# o_clone_rev_c.net
KiCad netlist of a schematic drawn in EAGLE
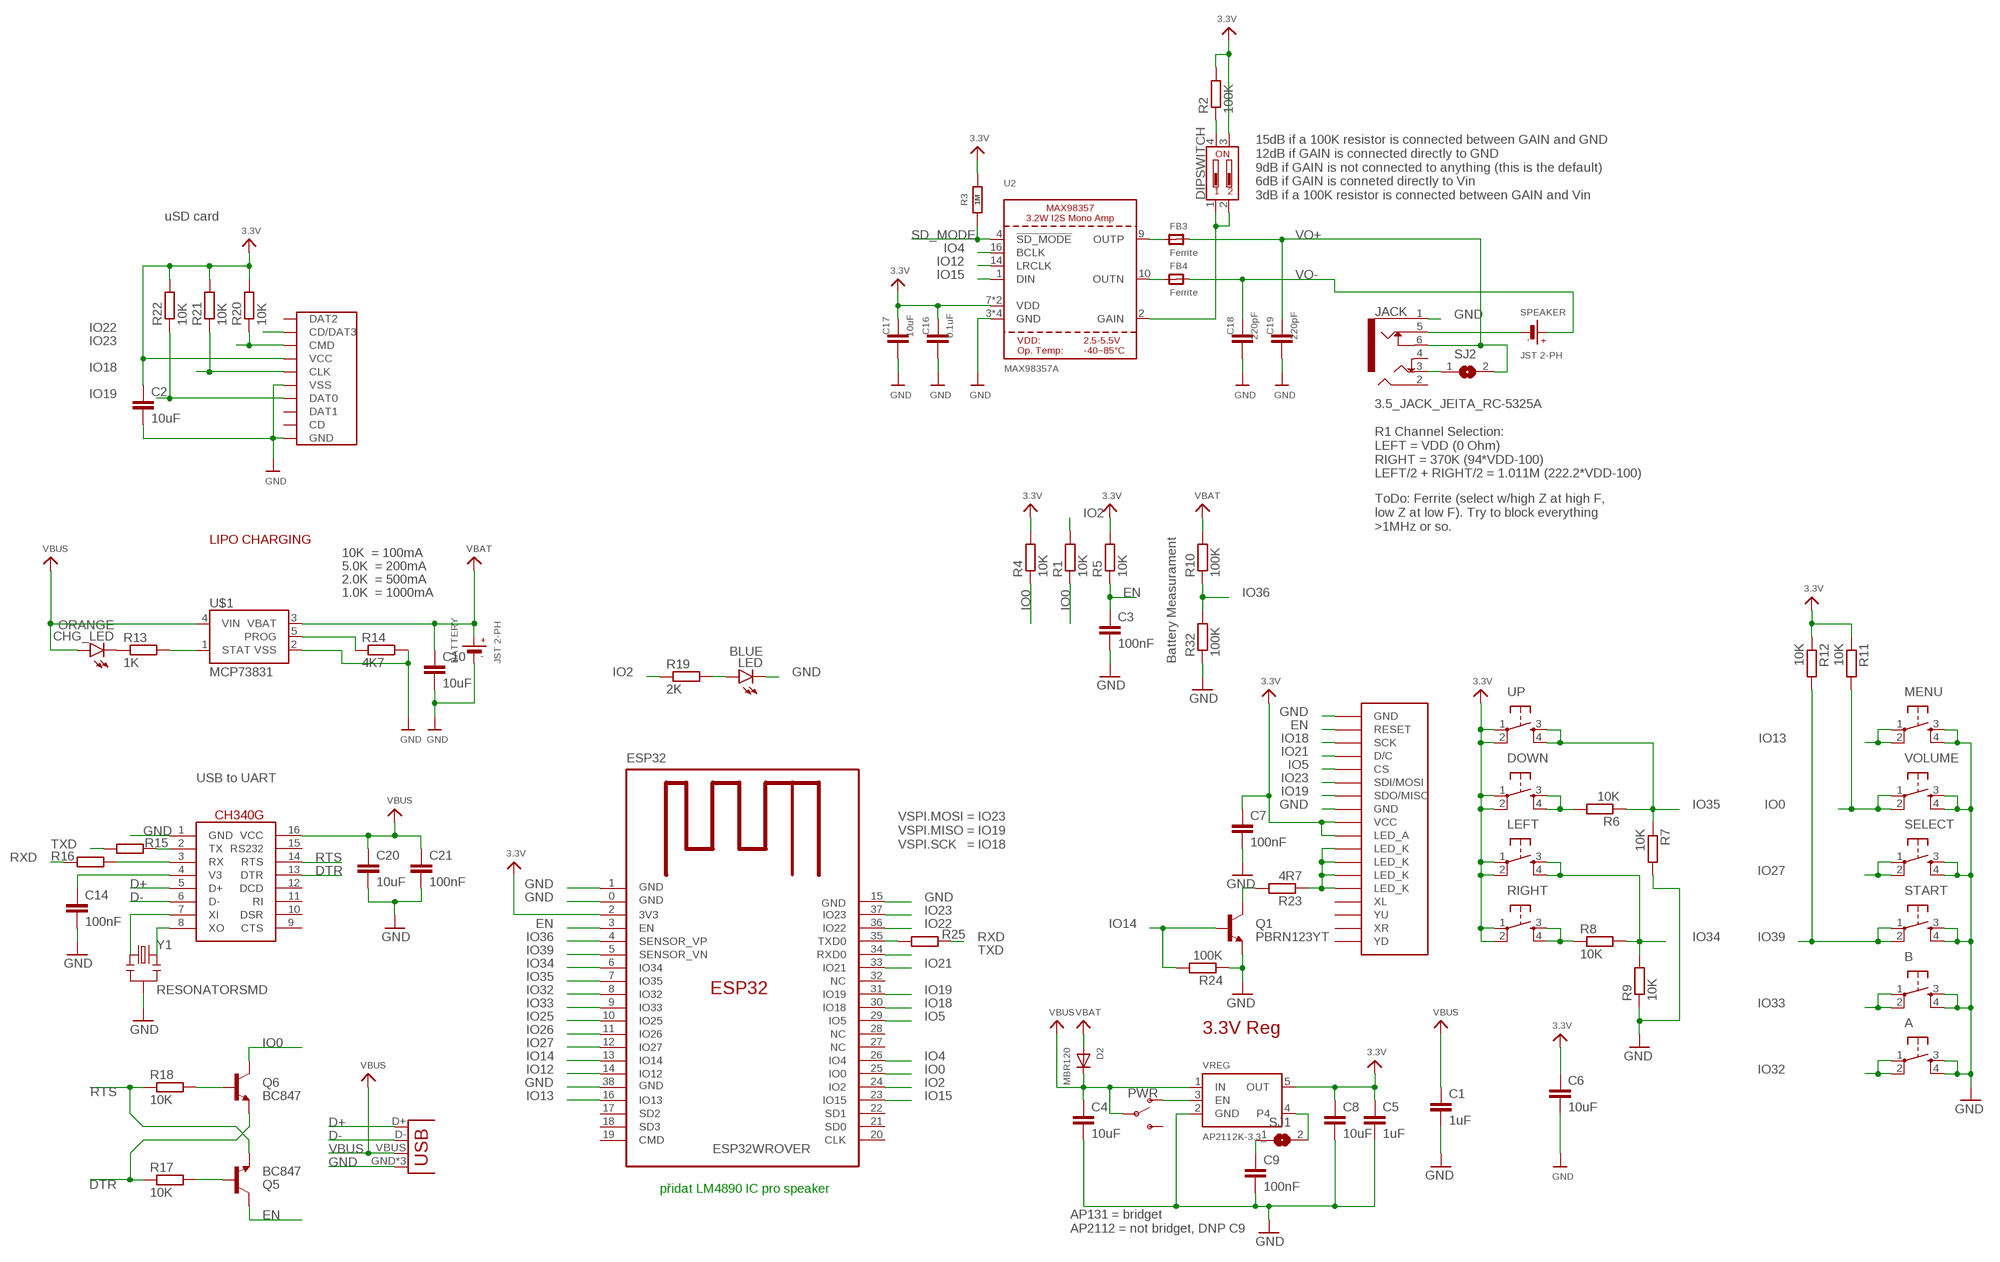
[diagram p0: schematic, sheet 1]

(export (version "E")
  (design (tool "Eeschema 10.0.6"))
  (components
    (comp (ref "A")
      (value "TACTILE_SWITCHE_5X5_MICRO\"")
      (footprint "eagle-import:TACTILE_SWITCH_5X5_MICRO")
      (libsource (lib "eagle-import") (part "TACTILE_SWITCHE_5X5_MICRO{dblquote}"))
    )
    (comp (ref "B")
      (value "TACTILE_SWITCHE_5X5_MICRO\"")
      (footprint "eagle-import:TACTILE_SWITCH_5X5_MICRO")
      (libsource (lib "eagle-import") (part "TACTILE_SWITCHE_5X5_MICRO{dblquote}"))
    )
    (comp (ref "BATTERY")
      (value "JST 2-PH")
      (footprint "eagle-import:JSTPH2")
      (libsource (lib "eagle-import") (part "JST_CONNECTOR"))
    )
    (comp (ref "C1")
      (value "1uF")
      (footprint "eagle-import:C0805")
      (libsource (lib "eagle-import") (part "C-EUC0805"))
    )
    (comp (ref "C2")
      (value "10uF")
      (footprint "eagle-import:C0805")
      (libsource (lib "eagle-import") (part "C-EUC0805"))
    )
    (comp (ref "C3")
      (value "100nF")
      (footprint "eagle-import:C0805")
      (libsource (lib "eagle-import") (part "C-EUC0805"))
    )
    (comp (ref "C4")
      (value "10uF")
      (footprint "eagle-import:C0805")
      (libsource (lib "eagle-import") (part "C-EUC0805"))
    )
    (comp (ref "C5")
      (value "1uF")
      (footprint "eagle-import:C0805")
      (libsource (lib "eagle-import") (part "C-EUC0805"))
    )
    (comp (ref "C6")
      (value "10uF")
      (footprint "eagle-import:C0805")
      (libsource (lib "eagle-import") (part "C-EUC0805"))
    )
    (comp (ref "C7")
      (value "100nF")
      (footprint "eagle-import:C0805")
      (libsource (lib "eagle-import") (part "C-EUC0805"))
    )
    (comp (ref "C8")
      (value "10uF")
      (footprint "eagle-import:C0805")
      (libsource (lib "eagle-import") (part "C-EUC0805"))
    )
    (comp (ref "C9")
      (value "100nF")
      (footprint "eagle-import:C0805")
      (libsource (lib "eagle-import") (part "C-EUC0805"))
    )
    (comp (ref "C10")
      (value "10uF")
      (footprint "eagle-import:C0805")
      (libsource (lib "eagle-import") (part "C-EUC0805"))
    )
    (comp (ref "C14")
      (value "100nF")
      (footprint "eagle-import:C0805")
      (libsource (lib "eagle-import") (part "C-EUC0805"))
    )
    (comp (ref "C16")
      (value "0.1uF")
      (footprint "eagle-import:C0805")
      (libsource (lib "eagle-import") (part "C-EUC0805"))
    )
    (comp (ref "C17")
      (value "10uF")
      (footprint "eagle-import:C0805")
      (libsource (lib "eagle-import") (part "C-EUC0805"))
    )
    (comp (ref "C18")
      (value "220pF")
      (footprint "eagle-import:C0805")
      (libsource (lib "eagle-import") (part "C-EUC0805"))
    )
    (comp (ref "C19")
      (value "220pF")
      (footprint "eagle-import:C0805")
      (libsource (lib "eagle-import") (part "C-EUC0805"))
    )
    (comp (ref "C20")
      (value "10uF")
      (footprint "eagle-import:C0805")
      (libsource (lib "eagle-import") (part "C-EUC0805"))
    )
    (comp (ref "C21")
      (value "100nF")
      (footprint "eagle-import:C0805")
      (libsource (lib "eagle-import") (part "C-EUC0805"))
    )
    (comp (ref "CHG_LED")
      (value "ORANGE")
      (footprint "eagle-import:CHIPLED_0805")
      (libsource (lib "eagle-import") (part "LEDCHIPLED_0805"))
    )
    (comp (ref "D2")
      (value "MBR120")
      (footprint "eagle-import:SOD-123")
      (libsource (lib "eagle-import") (part "DIODESOD-123"))
    )
    (comp (ref "DIPSWITCH")
      (value "DIP-02-SMD-50MIL")
      (footprint "eagle-import:DIPSWITCH-02-50MIL")
      (libsource (lib "eagle-import") (part "DIP-02-SMD-50MIL"))
    )
    (comp (ref "DOWN")
      (value "TACTILE_SWITCHE_5X5_MICRO\"")
      (footprint "eagle-import:TACTILE_SWITCH_5X5_MICRO")
      (libsource (lib "eagle-import") (part "TACTILE_SWITCHE_5X5_MICRO{dblquote}"))
    )
    (comp (ref "ESP32")
      (value "ESP32WROVER")
      (footprint "eagle-import:ESP32WROVER")
      (libsource (lib "eagle-import") (part "ESP32WROVER"))
    )
    (comp (ref "FB3")
      (value "Ferrite")
      (footprint "eagle-import:0805")
      (libsource (lib "eagle-import") (part "FERRITE0805"))
    )
    (comp (ref "FB4")
      (value "Ferrite")
      (footprint "eagle-import:0805")
      (libsource (lib "eagle-import") (part "FERRITE0805"))
    )
    (comp (ref "JACK")
      (value "3.5_JACK_JEITA_RC-5325A")
      (footprint "eagle-import:3.5_JACK_JEITA_RC-5325A")
      (libsource (lib "eagle-import") (part "3.5_JACK_JEITA_RC-5325A"))
    )
    (comp (ref "LCD")
      (value "ILI9341_3.2LCD_")
      (footprint "eagle-import:LI9341_3.2LCD")
      (libsource (lib "eagle-import") (part "ILI9341_3.2LCD_"))
    )
    (comp (ref "LED")
      (value "BLUE")
      (footprint "eagle-import:CHIPLED_0805")
      (libsource (lib "eagle-import") (part "LEDCHIPLED_0805"))
    )
    (comp (ref "LEFT")
      (value "TACTILE_SWITCHE_5X5_MICRO\"")
      (footprint "eagle-import:TACTILE_SWITCH_5X5_MICRO")
      (libsource (lib "eagle-import") (part "TACTILE_SWITCHE_5X5_MICRO{dblquote}"))
    )
    (comp (ref "MENU")
      (value "TACTILE_SWITCHE_5X5_MICRO\"")
      (footprint "eagle-import:TACTILE_SWITCH_5X5_MICRO")
      (libsource (lib "eagle-import") (part "TACTILE_SWITCHE_5X5_MICRO{dblquote}"))
    )
    (comp (ref "PWR")
      (value "SWITCH-SPDT-SMD-RIGHT-ANGLE")
      (footprint "eagle-import:SWITCH_SPST_SMD_A")
      (libsource (lib "eagle-import") (part "SWITCH-SPDT-SMD-RIGHT-ANGLE"))
    )
    (comp (ref "Q1")
      (value "PBRN123YT")
      (footprint "eagle-import:SOT23-3")
      (libsource (lib "eagle-import") (part "TRANSISTOR_NPNSOT23-3"))
    )
    (comp (ref "Q5")
      (value "BC847")
      (footprint "eagle-import:SOT23-3")
      (libsource (lib "eagle-import") (part "TRANSISTOR_NPNSOT23-3"))
    )
    (comp (ref "Q6")
      (value "BC847")
      (footprint "eagle-import:SOT23-3")
      (libsource (lib "eagle-import") (part "TRANSISTOR_NPNSOT23-3"))
    )
    (comp (ref "R1")
      (value "10K")
      (footprint "eagle-import:R0805")
      (libsource (lib "eagle-import") (part "R-EU_R0805"))
    )
    (comp (ref "R2")
      (value "100K")
      (footprint "eagle-import:R0805")
      (libsource (lib "eagle-import") (part "R-EU_R0805"))
    )
    (comp (ref "R3")
      (value "1M")
      (footprint "eagle-import:R0805")
      (libsource (lib "eagle-import") (part "R-EU_R0805"))
    )
    (comp (ref "R4")
      (value "10K")
      (footprint "eagle-import:R0805")
      (libsource (lib "eagle-import") (part "R-EU_R0805"))
    )
    (comp (ref "R5")
      (value "10K")
      (footprint "eagle-import:R0805")
      (libsource (lib "eagle-import") (part "R-EU_R0805"))
    )
    (comp (ref "R6")
      (value "10K")
      (footprint "eagle-import:R0805")
      (libsource (lib "eagle-import") (part "R-EU_R0805"))
    )
    (comp (ref "R7")
      (value "10K")
      (footprint "eagle-import:R0805")
      (libsource (lib "eagle-import") (part "R-EU_R0805"))
    )
    (comp (ref "R8")
      (value "10K")
      (footprint "eagle-import:R0805")
      (libsource (lib "eagle-import") (part "R-EU_R0805"))
    )
    (comp (ref "R9")
      (value "10K")
      (footprint "eagle-import:R0805")
      (libsource (lib "eagle-import") (part "R-EU_R0805"))
    )
    (comp (ref "R10")
      (value "100K")
      (footprint "eagle-import:R0805")
      (libsource (lib "eagle-import") (part "R-EU_R0805"))
    )
    (comp (ref "R11")
      (value "10K")
      (footprint "eagle-import:R0805")
      (libsource (lib "eagle-import") (part "R-EU_R0805"))
    )
    (comp (ref "R12")
      (value "10K")
      (footprint "eagle-import:R0805")
      (libsource (lib "eagle-import") (part "R-EU_R0805"))
    )
    (comp (ref "R13")
      (value "1K")
      (footprint "eagle-import:R0805")
      (libsource (lib "eagle-import") (part "R-EU_R0805"))
    )
    (comp (ref "R14")
      (value "4K7")
      (footprint "eagle-import:R0805")
      (libsource (lib "eagle-import") (part "R-EU_R0805"))
    )
    (comp (ref "R15")
      (value "470R")
      (footprint "eagle-import:R0805")
      (libsource (lib "eagle-import") (part "R-EU_R0805"))
    )
    (comp (ref "R16")
      (value "470R")
      (footprint "eagle-import:R0805")
      (libsource (lib "eagle-import") (part "R-EU_R0805"))
    )
    (comp (ref "R17")
      (value "10K")
      (footprint "eagle-import:R0805")
      (libsource (lib "eagle-import") (part "R-EU_R0805"))
    )
    (comp (ref "R18")
      (value "10K")
      (footprint "eagle-import:R0805")
      (libsource (lib "eagle-import") (part "R-EU_R0805"))
    )
    (comp (ref "R19")
      (value "2K")
      (footprint "eagle-import:R0805")
      (libsource (lib "eagle-import") (part "R-EU_R0805"))
    )
    (comp (ref "R20")
      (value "10K")
      (footprint "eagle-import:R0805")
      (libsource (lib "eagle-import") (part "R-EU_R0805"))
    )
    (comp (ref "R21")
      (value "10K")
      (footprint "eagle-import:R0805")
      (libsource (lib "eagle-import") (part "R-EU_R0805"))
    )
    (comp (ref "R22")
      (value "10K")
      (footprint "eagle-import:R0805")
      (libsource (lib "eagle-import") (part "R-EU_R0805"))
    )
    (comp (ref "R23")
      (value "4R7")
      (footprint "eagle-import:R0805")
      (libsource (lib "eagle-import") (part "R-EU_R0805"))
    )
    (comp (ref "R24")
      (value "100K")
      (footprint "eagle-import:R0805")
      (libsource (lib "eagle-import") (part "R-EU_R0805"))
    )
    (comp (ref "R25")
      (value "470R")
      (footprint "eagle-import:R0805")
      (libsource (lib "eagle-import") (part "R-EU_R0805"))
    )
    (comp (ref "R32")
      (value "100K")
      (footprint "eagle-import:R0805")
      (libsource (lib "eagle-import") (part "R-EU_R0805"))
    )
    (comp (ref "RIGHT")
      (value "TACTILE_SWITCHE_5X5_MICRO\"")
      (footprint "eagle-import:TACTILE_SWITCH_5X5_MICRO")
      (libsource (lib "eagle-import") (part "TACTILE_SWITCHE_5X5_MICRO{dblquote}"))
    )
    (comp (ref "SD_CARD")
      (value "MICRO_SD_CARD\"")
      (footprint "eagle-import:TFP09-2--12B")
      (libsource (lib "eagle-import") (part "MICRO_SD_CARD{dblquote}"))
    )
    (comp (ref "SELECT")
      (value "TACTILE_SWITCHE_5X5_MICRO\"")
      (footprint "eagle-import:TACTILE_SWITCH_5X5_MICRO")
      (libsource (lib "eagle-import") (part "TACTILE_SWITCHE_5X5_MICRO{dblquote}"))
    )
    (comp (ref "SJ1") (value "SJ") (footprint "eagle-import:SJ") (libsource (lib "eagle-import") (part "SJ")))
    (comp (ref "SJ2") (value "SJ") (footprint "eagle-import:SJ") (libsource (lib "eagle-import") (part "SJ")))
    (comp (ref "SPEAKER")
      (value "JST 2-PH")
      (footprint "eagle-import:JSTPH2")
      (libsource (lib "eagle-import") (part "JST_CONNECTOR"))
    )
    (comp (ref "START")
      (value "TACTILE_SWITCHE_5X5_MICRO\"")
      (footprint "eagle-import:TACTILE_SWITCH_5X5_MICRO")
      (libsource (lib "eagle-import") (part "TACTILE_SWITCHE_5X5_MICRO{dblquote}"))
    )
    (comp (ref "U$1")
      (value "MCP73831")
      (footprint "eagle-import:SOT95P290X120-5")
      (libsource (lib "eagle-import") (part "MCP73831"))
    )
    (comp (ref "U$23")
      (value "CH340G")
      (footprint "eagle-import:SO16")
      (libsource (lib "eagle-import") (part "CH340G"))
    )
    (comp (ref "U2")
      (value "MAX98357A")
      (footprint "eagle-import:QFN16_3MM")
      (libsource (lib "eagle-import") (part "AUDIOAMP_MAX98357"))
    )
    (comp (ref "UP")
      (value "TACTILE_SWITCHE_5X5_MICRO\"")
      (footprint "eagle-import:TACTILE_SWITCH_5X5_MICRO")
      (libsource (lib "eagle-import") (part "TACTILE_SWITCHE_5X5_MICRO{dblquote}"))
    )
    (comp (ref "USB")
      (value "USB_MICRO_ATTEND_")
      (footprint "eagle-import:USB_MICRO")
      (libsource (lib "eagle-import") (part "USB_MICRO_ATTEND_"))
    )
    (comp (ref "VOLUME")
      (value "TACTILE_SWITCHE_5X5_MICRO\"")
      (footprint "eagle-import:TACTILE_SWITCH_5X5_MICRO")
      (libsource (lib "eagle-import") (part "TACTILE_SWITCHE_5X5_MICRO{dblquote}"))
    )
    (comp (ref "VREG")
      (value "AP2112K-3.3_")
      (footprint "eagle-import:SOT95P290X120-5")
      (libsource (lib "eagle-import") (part "AP2112K-3.3_"))
    )
    (comp (ref "Y1")
      (value "RESONATORSMD")
      (footprint "eagle-import:RESONATOR-SMD")
      (libsource (lib "eagle-import") (part "RESONATORSMD"))
    )
  )
  (nets
    (net (code "1") (name "/D+") (class "Default")
      (node (ref "U$23") (pin "5") (pinfunction "D+_5") (pintype "bidirectional"))
      (node (ref "USB") (pin "D+") (pinfunction "D+_D+") (pintype "bidirectional"))
    )
    (net (code "2") (name "/D-") (class "Default")
      (node (ref "U$23") (pin "6") (pinfunction "D-_6") (pintype "bidirectional"))
      (node (ref "USB") (pin "D-") (pinfunction "D-_D-") (pintype "bidirectional"))
    )
    (net (code "3") (name "/DTR") (class "Default")
      (node (ref "Q6") (pin "2") (pinfunction "E_2") (pintype "passive"))
      (node (ref "R17") (pin "1") (pinfunction "1_1") (pintype "passive"))
      (node (ref "U$23") (pin "13") (pinfunction "DTR_13") (pintype "bidirectional"))
    )
    (net (code "4") (name "/EN") (class "Default")
      (node (ref "C3") (pin "1") (pinfunction "1_1") (pintype "passive"))
      (node (ref "ESP32") (pin "3") (pinfunction "EN_3") (pintype "bidirectional"))
      (node (ref "LCD") (pin "P$2") (pinfunction "RESET_P$2") (pintype "bidirectional"))
      (node (ref "Q5") (pin "3") (pinfunction "C_3") (pintype "passive"))
      (node (ref "R5") (pin "1") (pinfunction "1_1") (pintype "passive"))
    )
    (net (code "5") (name "/IO0") (class "Default")
      (node (ref "ESP32") (pin "25") (pinfunction "IO0_25") (pintype "bidirectional"))
      (node (ref "Q6") (pin "3") (pinfunction "C_3") (pintype "passive"))
      (node (ref "R1") (pin "1") (pinfunction "1_1") (pintype "passive"))
      (node (ref "R11") (pin "2") (pinfunction "2_2") (pintype "passive"))
      (node (ref "R4") (pin "1") (pinfunction "1_1") (pintype "passive"))
      (node (ref "VOLUME") (pin "1") (pinfunction "1_1") (pintype "passive"))
      (node (ref "VOLUME") (pin "2") (pinfunction "2_2") (pintype "passive"))
    )
    (net (code "6") (name "/IO2") (class "Default")
      (node (ref "ESP32") (pin "24") (pinfunction "IO2_24") (pintype "bidirectional"))
      (node (ref "R1") (pin "2") (pinfunction "2_2") (pintype "passive"))
      (node (ref "R19") (pin "1") (pinfunction "1_1") (pintype "passive"))
    )
    (net (code "7") (name "/IO4") (class "Default")
      (node (ref "ESP32") (pin "26") (pinfunction "IO4_26") (pintype "bidirectional"))
      (node (ref "U2") (pin "16") (pinfunction "BCLK_16") (pintype "bidirectional"))
    )
    (net (code "8") (name "/IO5") (class "Default")
      (node (ref "ESP32") (pin "29") (pinfunction "IO5_29") (pintype "bidirectional"))
      (node (ref "LCD") (pin "P$5") (pinfunction "CS_P$5") (pintype "bidirectional"))
    )
    (net (code "9") (name "/IO12") (class "Default")
      (node (ref "ESP32") (pin "14") (pinfunction "IO12_14") (pintype "bidirectional"))
      (node (ref "U2") (pin "14") (pinfunction "LRCLK_14") (pintype "bidirectional"))
    )
    (net (code "10") (name "/IO13") (class "Default")
      (node (ref "ESP32") (pin "16") (pinfunction "IO13_16") (pintype "bidirectional"))
      (node (ref "MENU") (pin "1") (pinfunction "1_1") (pintype "passive"))
      (node (ref "MENU") (pin "2") (pinfunction "2_2") (pintype "passive"))
    )
    (net (code "11") (name "/IO14") (class "Default")
      (node (ref "ESP32") (pin "13") (pinfunction "IO14_13") (pintype "bidirectional"))
      (node (ref "Q1") (pin "1") (pinfunction "B_1") (pintype "passive"))
      (node (ref "R24") (pin "2") (pinfunction "2_2") (pintype "passive"))
    )
    (net (code "12") (name "/IO15") (class "Default")
      (node (ref "ESP32") (pin "23") (pinfunction "IO15_23") (pintype "bidirectional"))
      (node (ref "U2") (pin "1") (pinfunction "DIN_1") (pintype "bidirectional"))
    )
    (net (code "13") (name "/IO18") (class "Default")
      (node (ref "ESP32") (pin "30") (pinfunction "IO18_30") (pintype "bidirectional"))
      (node (ref "LCD") (pin "P$3") (pinfunction "SCK_P$3") (pintype "bidirectional"))
      (node (ref "R21") (pin "1") (pinfunction "1_1") (pintype "passive"))
      (node (ref "SD_CARD") (pin "CLK") (pinfunction "CLK_CLK") (pintype "bidirectional"))
    )
    (net (code "14") (name "/IO19") (class "Default")
      (node (ref "ESP32") (pin "31") (pinfunction "IO19_31") (pintype "bidirectional"))
      (node (ref "LCD") (pin "P$7") (pinfunction "SDO/MISO_P$7") (pintype "bidirectional"))
      (node (ref "R22") (pin "1") (pinfunction "1_1") (pintype "passive"))
      (node (ref "SD_CARD") (pin "DAT0") (pinfunction "DAT0_DAT0") (pintype "bidirectional"))
    )
    (net (code "15") (name "/IO21") (class "Default")
      (node (ref "ESP32") (pin "33") (pinfunction "IO21_33") (pintype "bidirectional"))
      (node (ref "LCD") (pin "P$4") (pinfunction "D/C_P$4") (pintype "bidirectional"))
    )
    (net (code "16") (name "/IO22") (class "Default")
      (node (ref "ESP32") (pin "36") (pinfunction "IO22_36") (pintype "bidirectional"))
      (node (ref "SD_CARD") (pin "CD/DAT3") (pinfunction "CD/DAT3_CD/DAT3") (pintype "bidirectional"))
    )
    (net (code "17") (name "/IO23") (class "Default")
      (node (ref "ESP32") (pin "37") (pinfunction "IO23_37") (pintype "bidirectional"))
      (node (ref "LCD") (pin "P$6") (pinfunction "SDI/MOSI_P$6") (pintype "bidirectional"))
      (node (ref "R20") (pin "1") (pinfunction "1_1") (pintype "passive"))
      (node (ref "SD_CARD") (pin "CMD") (pinfunction "CMD_CMD") (pintype "bidirectional"))
    )
    (net (code "18") (name "/IO25") (class "Default")
      (node (ref "ESP32") (pin "10") (pinfunction "IO25_10") (pintype "bidirectional"))
    )
    (net (code "19") (name "/IO26") (class "Default")
      (node (ref "ESP32") (pin "11") (pinfunction "IO26_11") (pintype "bidirectional"))
    )
    (net (code "20") (name "/IO27") (class "Default")
      (node (ref "ESP32") (pin "12") (pinfunction "IO27_12") (pintype "bidirectional"))
      (node (ref "SELECT") (pin "1") (pinfunction "1_1") (pintype "passive"))
      (node (ref "SELECT") (pin "2") (pinfunction "2_2") (pintype "passive"))
    )
    (net (code "21") (name "/IO32") (class "Default")
      (node (ref "A") (pin "1") (pinfunction "1_1") (pintype "passive"))
      (node (ref "A") (pin "2") (pinfunction "2_2") (pintype "passive"))
      (node (ref "ESP32") (pin "8") (pinfunction "IO32_8") (pintype "bidirectional"))
    )
    (net (code "22") (name "/IO33") (class "Default")
      (node (ref "B") (pin "1") (pinfunction "1_1") (pintype "passive"))
      (node (ref "B") (pin "2") (pinfunction "2_2") (pintype "passive"))
      (node (ref "ESP32") (pin "9") (pinfunction "IO33_9") (pintype "bidirectional"))
    )
    (net (code "23") (name "/IO34") (class "Default")
      (node (ref "ESP32") (pin "6") (pinfunction "IO34_6") (pintype "bidirectional"))
      (node (ref "LEFT") (pin "3") (pinfunction "3_3") (pintype "passive"))
      (node (ref "LEFT") (pin "4") (pinfunction "4_4") (pintype "passive"))
      (node (ref "R8") (pin "2") (pinfunction "2_2") (pintype "passive"))
      (node (ref "R9") (pin "2") (pinfunction "2_2") (pintype "passive"))
    )
    (net (code "24") (name "/IO35") (class "Default")
      (node (ref "ESP32") (pin "7") (pinfunction "IO35_7") (pintype "bidirectional"))
      (node (ref "R6") (pin "1") (pinfunction "1_1") (pintype "passive"))
      (node (ref "R7") (pin "1") (pinfunction "1_1") (pintype "passive"))
      (node (ref "UP") (pin "3") (pinfunction "3_3") (pintype "passive"))
      (node (ref "UP") (pin "4") (pinfunction "4_4") (pintype "passive"))
    )
    (net (code "25") (name "/IO36") (class "Default")
      (node (ref "ESP32") (pin "4") (pinfunction "SENSOR_VP_4") (pintype "bidirectional"))
      (node (ref "R10") (pin "1") (pinfunction "1_1") (pintype "passive"))
      (node (ref "R32") (pin "2") (pinfunction "2_2") (pintype "passive"))
    )
    (net (code "26") (name "/IO39") (class "Default")
      (node (ref "ESP32") (pin "5") (pinfunction "SENSOR_VN_5") (pintype "bidirectional"))
      (node (ref "R12") (pin "2") (pinfunction "2_2") (pintype "passive"))
      (node (ref "START") (pin "1") (pinfunction "1_1") (pintype "passive"))
      (node (ref "START") (pin "2") (pinfunction "2_2") (pintype "passive"))
    )
    (net (code "27") (name "/RTS") (class "Default")
      (node (ref "Q5") (pin "2") (pinfunction "E_2") (pintype "passive"))
      (node (ref "R18") (pin "1") (pinfunction "1_1") (pintype "passive"))
      (node (ref "U$23") (pin "14") (pinfunction "RTS_14") (pintype "bidirectional"))
    )
    (net (code "28") (name "/RXD") (class "Default")
      (node (ref "R16") (pin "2") (pinfunction "2_2") (pintype "passive"))
      (node (ref "R25") (pin "1") (pinfunction "1_1") (pintype "passive"))
    )
    (net (code "29") (name "/SD_MODE") (class "Default")
      (node (ref "R3") (pin "1") (pinfunction "1_1") (pintype "passive"))
      (node (ref "U2") (pin "4") (pinfunction "~{SD_MODE}_4") (pintype "bidirectional"))
    )
    (net (code "30") (name "/TXD") (class "Default")
      (node (ref "ESP32") (pin "34") (pinfunction "RXD0_34") (pintype "bidirectional"))
      (node (ref "R15") (pin "2") (pinfunction "2_2") (pintype "passive"))
    )
    (net (code "31") (name "/VO+") (class "Default")
      (node (ref "C19") (pin "1") (pinfunction "1_1") (pintype "passive"))
      (node (ref "FB3") (pin "2") (pinfunction "P$2_2") (pintype "passive"))
      (node (ref "JACK") (pin "6") (pinfunction "6_6") (pintype "bidirectional"))
      (node (ref "SJ2") (pin "2") (pinfunction "2_2") (pintype "passive"))
    )
    (net (code "32") (name "/VO-") (class "Default")
      (node (ref "C18") (pin "1") (pinfunction "1_1") (pintype "passive"))
      (node (ref "FB4") (pin "2") (pinfunction "P$2_2") (pintype "passive"))
      (node (ref "SPEAKER") (pin "2") (pinfunction "+_2") (pintype "passive"))
    )
    (net (code "33") (name "3.3V") (class "Default")
      (node (ref "C16") (pin "1") (pinfunction "1_1") (pintype "passive"))
      (node (ref "C17") (pin "1") (pinfunction "1_1") (pintype "passive"))
      (node (ref "C2") (pin "1") (pinfunction "1_1") (pintype "passive"))
      (node (ref "C5") (pin "1") (pinfunction "1_1") (pintype "passive"))
      (node (ref "C6") (pin "1") (pinfunction "1_1") (pintype "passive"))
      (node (ref "C7") (pin "1") (pinfunction "1_1") (pintype "passive"))
      (node (ref "C8") (pin "1") (pinfunction "1_1") (pintype "passive"))
      (node (ref "DIPSWITCH") (pin "3") (pinfunction "P$3_3") (pintype "bidirectional"))
      (node (ref "DOWN") (pin "1") (pinfunction "1_1") (pintype "passive"))
      (node (ref "DOWN") (pin "2") (pinfunction "2_2") (pintype "passive"))
      (node (ref "ESP32") (pin "2") (pinfunction "3V3_2") (pintype "power_in"))
      (node (ref "LCD") (pin "P$10") (pinfunction "LED_A_P$10") (pintype "bidirectional"))
      (node (ref "LCD") (pin "P$9") (pinfunction "VCC_P$9") (pintype "bidirectional"))
      (node (ref "LEFT") (pin "1") (pinfunction "1_1") (pintype "passive"))
      (node (ref "LEFT") (pin "2") (pinfunction "2_2") (pintype "passive"))
      (node (ref "R11") (pin "1") (pinfunction "1_1") (pintype "passive"))
      (node (ref "R12") (pin "1") (pinfunction "1_1") (pintype "passive"))
      (node (ref "R2") (pin "2") (pinfunction "2_2") (pintype "passive"))
      (node (ref "R20") (pin "2") (pinfunction "2_2") (pintype "passive"))
      (node (ref "R21") (pin "2") (pinfunction "2_2") (pintype "passive"))
      (node (ref "R22") (pin "2") (pinfunction "2_2") (pintype "passive"))
      (node (ref "R3") (pin "2") (pinfunction "2_2") (pintype "passive"))
      (node (ref "R4") (pin "2") (pinfunction "2_2") (pintype "passive"))
      (node (ref "R5") (pin "2") (pinfunction "2_2") (pintype "passive"))
      (node (ref "RIGHT") (pin "1") (pinfunction "1_1") (pintype "passive"))
      (node (ref "RIGHT") (pin "2") (pinfunction "2_2") (pintype "passive"))
      (node (ref "SD_CARD") (pin "VCC") (pinfunction "VCC_VCC") (pintype "bidirectional"))
      (node (ref "U2") (pin "7") (pinfunction "VDD_7") (pintype "power_in"))
      (node (ref "U2") (pin "8") (pinfunction "VDD_8") (pintype "power_in"))
      (node (ref "UP") (pin "1") (pinfunction "1_1") (pintype "passive"))
      (node (ref "UP") (pin "2") (pinfunction "2_2") (pintype "passive"))
      (node (ref "VREG") (pin "5") (pinfunction "OUT_5") (pintype "bidirectional"))
    )
    (net (code "34") (name "GND") (class "Default")
      (node (ref "A") (pin "3") (pinfunction "3_3") (pintype "passive"))
      (node (ref "A") (pin "4") (pinfunction "4_4") (pintype "passive"))
      (node (ref "B") (pin "3") (pinfunction "3_3") (pintype "passive"))
      (node (ref "B") (pin "4") (pinfunction "4_4") (pintype "passive"))
      (node (ref "BATTERY") (pin "1") (pinfunction "-_1") (pintype "passive"))
      (node (ref "C1") (pin "2") (pinfunction "2_2") (pintype "passive"))
      (node (ref "C10") (pin "2") (pinfunction "2_2") (pintype "passive"))
      (node (ref "C14") (pin "2") (pinfunction "2_2") (pintype "passive"))
      (node (ref "C16") (pin "2") (pinfunction "2_2") (pintype "passive"))
      (node (ref "C17") (pin "2") (pinfunction "2_2") (pintype "passive"))
      (node (ref "C18") (pin "2") (pinfunction "2_2") (pintype "passive"))
      (node (ref "C19") (pin "2") (pinfunction "2_2") (pintype "passive"))
      (node (ref "C2") (pin "2") (pinfunction "2_2") (pintype "passive"))
      (node (ref "C20") (pin "2") (pinfunction "2_2") (pintype "passive"))
      (node (ref "C21") (pin "2") (pinfunction "2_2") (pintype "passive"))
      (node (ref "C3") (pin "2") (pinfunction "2_2") (pintype "passive"))
      (node (ref "C4") (pin "2") (pinfunction "2_2") (pintype "passive"))
      (node (ref "C5") (pin "2") (pinfunction "2_2") (pintype "passive"))
      (node (ref "C6") (pin "2") (pinfunction "2_2") (pintype "passive"))
      (node (ref "C7") (pin "2") (pinfunction "2_2") (pintype "passive"))
      (node (ref "C8") (pin "2") (pinfunction "2_2") (pintype "passive"))
      (node (ref "C9") (pin "2") (pinfunction "2_2") (pintype "passive"))
      (node (ref "ESP32") (pin "0") (pinfunction "GND_0") (pintype "power_in"))
      (node (ref "ESP32") (pin "1") (pinfunction "GND_1") (pintype "power_in"))
      (node (ref "ESP32") (pin "15") (pinfunction "GND_15") (pintype "power_in"))
      (node (ref "ESP32") (pin "38") (pinfunction "GND_38") (pintype "power_in"))
      (node (ref "JACK") (pin "1") (pinfunction "1_1") (pintype "bidirectional"))
      (node (ref "LCD") (pin "P$1") (pinfunction "GND_P$1") (pintype "bidirectional"))
      (node (ref "LCD") (pin "P$8") (pinfunction "GND_P$8") (pintype "bidirectional"))
      (node (ref "LED") (pin "C") (pinfunction "C_C") (pintype "passive"))
      (node (ref "MENU") (pin "3") (pinfunction "3_3") (pintype "passive"))
      (node (ref "MENU") (pin "4") (pinfunction "4_4") (pintype "passive"))
      (node (ref "Q1") (pin "2") (pinfunction "E_2") (pintype "passive"))
      (node (ref "R14") (pin "2") (pinfunction "2_2") (pintype "passive"))
      (node (ref "R24") (pin "1") (pinfunction "1_1") (pintype "passive"))
      (node (ref "R32") (pin "1") (pinfunction "1_1") (pintype "passive"))
      (node (ref "R7") (pin "2") (pinfunction "2_2") (pintype "passive"))
      (node (ref "R9") (pin "1") (pinfunction "1_1") (pintype "passive"))
      (node (ref "SD_CARD") (pin "GND") (pinfunction "GND_GND") (pintype "bidirectional"))
      (node (ref "SD_CARD") (pin "GND@1") (pinfunction "GND_GND@1") (pintype "bidirectional"))
      (node (ref "SD_CARD") (pin "GND@2") (pinfunction "GND_GND@2") (pintype "bidirectional"))
      (node (ref "SD_CARD") (pin "GND@3") (pinfunction "VSS_GND@3") (pintype "bidirectional"))
      (node (ref "SD_CARD") (pin "VSS") (pinfunction "GND_VSS") (pintype "bidirectional"))
      (node (ref "SELECT") (pin "3") (pinfunction "3_3") (pintype "passive"))
      (node (ref "SELECT") (pin "4") (pinfunction "4_4") (pintype "passive"))
      (node (ref "START") (pin "3") (pinfunction "3_3") (pintype "passive"))
      (node (ref "START") (pin "4") (pinfunction "4_4") (pintype "passive"))
      (node (ref "U$1") (pin "2") (pinfunction "VSS_2") (pintype "power_in"))
      (node (ref "U$23") (pin "1") (pinfunction "GND_1") (pintype "bidirectional"))
      (node (ref "U2") (pin "11") (pinfunction "GND_11") (pintype "power_in"))
      (node (ref "U2") (pin "15") (pinfunction "GND_15") (pintype "power_in"))
      (node (ref "U2") (pin "3") (pinfunction "GND_3") (pintype "power_in"))
      (node (ref "U2") (pin "THERMAL") (pinfunction "GND_THERMAL") (pintype "power_in"))
      (node (ref "USB") (pin "GND") (pinfunction "GND_GND") (pintype "bidirectional"))
      (node (ref "USB") (pin "GND@2") (pinfunction "GND_GND@2") (pintype "bidirectional"))
      (node (ref "USB") (pin "GND@3") (pinfunction "GND_GND@3") (pintype "bidirectional"))
      (node (ref "VOLUME") (pin "3") (pinfunction "3_3") (pintype "passive"))
      (node (ref "VOLUME") (pin "4") (pinfunction "4_4") (pintype "passive"))
      (node (ref "VREG") (pin "2") (pinfunction "GND_2") (pintype "bidirectional"))
      (node (ref "Y1") (pin "2") (pinfunction "2_2") (pintype "passive"))
    )
    (net (code "35") (name "Net-(C9-Pad1)") (class "Default")
      (node (ref "C9") (pin "1") (pinfunction "1_1") (pintype "passive"))
      (node (ref "SJ1") (pin "1") (pinfunction "1_1") (pintype "passive"))
    )
    (net (code "36") (name "Net-(CHG_LED-PadC)") (class "Default")
      (node (ref "CHG_LED") (pin "C") (pinfunction "C_C") (pintype "passive"))
      (node (ref "R13") (pin "1") (pinfunction "1_1") (pintype "passive"))
    )
    (net (code "37") (name "Net-(DIPSWITCH-P$1)") (class "Default")
      (node (ref "DIPSWITCH") (pin "1") (pinfunction "P$1_1") (pintype "bidirectional"))
      (node (ref "DIPSWITCH") (pin "2") (pinfunction "P$2_2") (pintype "bidirectional"))
      (node (ref "U2") (pin "2") (pinfunction "GAIN_2") (pintype "bidirectional"))
    )
    (net (code "38") (name "Net-(DIPSWITCH-P$4)") (class "Default")
      (node (ref "DIPSWITCH") (pin "4") (pinfunction "P$4_4") (pintype "bidirectional"))
      (node (ref "R2") (pin "1") (pinfunction "1_1") (pintype "passive"))
    )
    (net (code "39") (name "Net-(DOWN-Pad3)") (class "Default")
      (node (ref "DOWN") (pin "3") (pinfunction "3_3") (pintype "passive"))
      (node (ref "DOWN") (pin "4") (pinfunction "4_4") (pintype "passive"))
      (node (ref "R6") (pin "2") (pinfunction "2_2") (pintype "passive"))
    )
    (net (code "40") (name "Net-(ESP32-TXD0)") (class "Default")
      (node (ref "ESP32") (pin "35") (pinfunction "TXD0_35") (pintype "bidirectional"))
      (node (ref "R25") (pin "2") (pinfunction "2_2") (pintype "passive"))
    )
    (net (code "41") (name "Net-(FB3-P$1)") (class "Default")
      (node (ref "FB3") (pin "1") (pinfunction "P$1_1") (pintype "passive"))
      (node (ref "U2") (pin "9") (pinfunction "OUTP_9") (pintype "output"))
    )
    (net (code "42") (name "Net-(FB4-P$1)") (class "Default")
      (node (ref "FB4") (pin "1") (pinfunction "P$1_1") (pintype "passive"))
      (node (ref "U2") (pin "10") (pinfunction "OUTN_10") (pintype "output"))
    )
    (net (code "43") (name "Net-(JACK-Pad3)") (class "Default")
      (node (ref "JACK") (pin "3") (pinfunction "3_3") (pintype "bidirectional"))
      (node (ref "SJ2") (pin "1") (pinfunction "1_1") (pintype "passive"))
    )
    (net (code "44") (name "Net-(LCD-LED_K-PadP$11)") (class "Default")
      (node (ref "LCD") (pin "P$11") (pinfunction "LED_K_P$11") (pintype "bidirectional"))
      (node (ref "LCD") (pin "P$12") (pinfunction "LED_K_P$12") (pintype "bidirectional"))
      (node (ref "LCD") (pin "P$13") (pinfunction "LED_K_P$13") (pintype "bidirectional"))
      (node (ref "LCD") (pin "P$14") (pinfunction "LED_K_P$14") (pintype "bidirectional"))
      (node (ref "R23") (pin "1") (pinfunction "1_1") (pintype "passive"))
    )
    (net (code "45") (name "Net-(LED-PadA)") (class "Default")
      (node (ref "LED") (pin "A") (pinfunction "A_A") (pintype "passive"))
      (node (ref "R19") (pin "2") (pinfunction "2_2") (pintype "passive"))
    )
    (net (code "46") (name "Net-(PWR-O)") (class "Default")
      (node (ref "PWR") (pin "1") (pinfunction "O_1") (pintype "passive"))
      (node (ref "VREG") (pin "3") (pinfunction "EN_3") (pintype "bidirectional"))
    )
    (net (code "47") (name "Net-(Q1-C)") (class "Default")
      (node (ref "Q1") (pin "3") (pinfunction "C_3") (pintype "passive"))
      (node (ref "R23") (pin "2") (pinfunction "2_2") (pintype "passive"))
    )
    (net (code "48") (name "Net-(Q5-B)") (class "Default")
      (node (ref "Q5") (pin "1") (pinfunction "B_1") (pintype "passive"))
      (node (ref "R17") (pin "2") (pinfunction "2_2") (pintype "passive"))
    )
    (net (code "49") (name "Net-(Q6-B)") (class "Default")
      (node (ref "Q6") (pin "1") (pinfunction "B_1") (pintype "passive"))
      (node (ref "R18") (pin "2") (pinfunction "2_2") (pintype "passive"))
    )
    (net (code "50") (name "Net-(R8-Pad1)") (class "Default")
      (node (ref "R8") (pin "1") (pinfunction "1_1") (pintype "passive"))
      (node (ref "RIGHT") (pin "3") (pinfunction "3_3") (pintype "passive"))
      (node (ref "RIGHT") (pin "4") (pinfunction "4_4") (pintype "passive"))
    )
    (net (code "51") (name "Net-(SPEAKER--)") (class "Default")
      (node (ref "JACK") (pin "5") (pinfunction "5_5") (pintype "bidirectional"))
      (node (ref "SPEAKER") (pin "1") (pinfunction "-_1") (pintype "passive"))
    )
    (net (code "52") (name "Net-(U$1-PROG)") (class "Default")
      (node (ref "R14") (pin "1") (pinfunction "1_1") (pintype "passive"))
      (node (ref "U$1") (pin "5") (pinfunction "PROG_5") (pintype "input"))
    )
    (net (code "53") (name "Net-(U$1-STAT)") (class "Default")
      (node (ref "R13") (pin "2") (pinfunction "2_2") (pintype "passive"))
      (node (ref "U$1") (pin "1") (pinfunction "STAT_1") (pintype "output"))
    )
    (net (code "54") (name "Net-(U$23-RX)") (class "Default")
      (node (ref "R16") (pin "1") (pinfunction "1_1") (pintype "passive"))
      (node (ref "U$23") (pin "3") (pinfunction "RX_3") (pintype "bidirectional"))
    )
    (net (code "55") (name "Net-(U$23-TX)") (class "Default")
      (node (ref "R15") (pin "1") (pinfunction "1_1") (pintype "passive"))
      (node (ref "U$23") (pin "2") (pinfunction "TX_2") (pintype "bidirectional"))
    )
    (net (code "56") (name "Net-(U$23-V3)") (class "Default")
      (node (ref "C14") (pin "1") (pinfunction "1_1") (pintype "passive"))
      (node (ref "U$23") (pin "4") (pinfunction "V3_4") (pintype "bidirectional"))
    )
    (net (code "57") (name "Net-(U$23-XI)") (class "Default")
      (node (ref "U$23") (pin "7") (pinfunction "XI_7") (pintype "bidirectional"))
      (node (ref "Y1") (pin "1") (pinfunction "1_1") (pintype "passive"))
    )
    (net (code "58") (name "Net-(U$23-XO)") (class "Default")
      (node (ref "U$23") (pin "8") (pinfunction "XO_8") (pintype "bidirectional"))
      (node (ref "Y1") (pin "3") (pinfunction "3_3") (pintype "passive"))
    )
    (net (code "59") (name "Net-(VREG-P4)") (class "Default")
      (node (ref "SJ1") (pin "2") (pinfunction "2_2") (pintype "passive"))
      (node (ref "VREG") (pin "4") (pinfunction "P4_4") (pintype "bidirectional"))
    )
    (net (code "60") (name "VBAT") (class "Default")
      (node (ref "BATTERY") (pin "2") (pinfunction "+_2") (pintype "passive"))
      (node (ref "C10") (pin "1") (pinfunction "1_1") (pintype "passive"))
      (node (ref "D2") (pin "A") (pinfunction "A_A") (pintype "passive"))
      (node (ref "R10") (pin "2") (pinfunction "2_2") (pintype "passive"))
      (node (ref "U$1") (pin "3") (pinfunction "VBAT_3") (pintype "power_in"))
    )
    (net (code "61") (name "VBUS") (class "Default")
      (node (ref "C1") (pin "1") (pinfunction "1_1") (pintype "passive"))
      (node (ref "C20") (pin "1") (pinfunction "1_1") (pintype "passive"))
      (node (ref "C21") (pin "1") (pinfunction "1_1") (pintype "passive"))
      (node (ref "C4") (pin "1") (pinfunction "1_1") (pintype "passive"))
      (node (ref "CHG_LED") (pin "A") (pinfunction "A_A") (pintype "passive"))
      (node (ref "D2") (pin "C") (pinfunction "C_C") (pintype "passive"))
      (node (ref "PWR") (pin "2") (pinfunction "P_2") (pintype "passive"))
      (node (ref "U$1") (pin "4") (pinfunction "VIN_4") (pintype "power_in"))
      (node (ref "U$23") (pin "16") (pinfunction "VCC_16") (pintype "bidirectional"))
      (node (ref "USB") (pin "VBUS") (pinfunction "VBUS_VBUS") (pintype "bidirectional"))
      (node (ref "VREG") (pin "1") (pinfunction "IN_1") (pintype "bidirectional"))
    )
    (net (code "62") (name "unconnected-(ESP32-CLK-Pad20)") (class "Default")
      (node (ref "ESP32") (pin "20") (pinfunction "CLK_20") (pintype "bidirectional"))
    )
    (net (code "63") (name "unconnected-(ESP32-CMD-Pad19)") (class "Default")
      (node (ref "ESP32") (pin "19") (pinfunction "CMD_19") (pintype "bidirectional"))
    )
    (net (code "64") (name "unconnected-(ESP32-NC-Pad27)") (class "Default")
      (node (ref "ESP32") (pin "27") (pinfunction "NC_27") (pintype "bidirectional"))
    )
    (net (code "65") (name "unconnected-(ESP32-NC-Pad28)") (class "Default")
      (node (ref "ESP32") (pin "28") (pinfunction "NC_28") (pintype "bidirectional"))
    )
    (net (code "66") (name "unconnected-(ESP32-NC-Pad32)") (class "Default")
      (node (ref "ESP32") (pin "32") (pinfunction "NC_32") (pintype "bidirectional"))
    )
    (net (code "67") (name "unconnected-(ESP32-SD0-Pad21)") (class "Default")
      (node (ref "ESP32") (pin "21") (pinfunction "SD0_21") (pintype "bidirectional"))
    )
    (net (code "68") (name "unconnected-(ESP32-SD1-Pad22)") (class "Default")
      (node (ref "ESP32") (pin "22") (pinfunction "SD1_22") (pintype "bidirectional"))
    )
    (net (code "69") (name "unconnected-(ESP32-SD2-Pad17)") (class "Default")
      (node (ref "ESP32") (pin "17") (pinfunction "SD2_17") (pintype "bidirectional"))
    )
    (net (code "70") (name "unconnected-(ESP32-SD3-Pad18)") (class "Default")
      (node (ref "ESP32") (pin "18") (pinfunction "SD3_18") (pintype "bidirectional"))
    )
    (net (code "71") (name "unconnected-(JACK-Pad2)") (class "Default")
      (node (ref "JACK") (pin "2") (pinfunction "2_2") (pintype "bidirectional"))
    )
    (net (code "72") (name "unconnected-(JACK-Pad4)") (class "Default")
      (node (ref "JACK") (pin "4") (pinfunction "4_4") (pintype "bidirectional"))
    )
    (net (code "73") (name "unconnected-(LCD-XL-PadP$15)") (class "Default")
      (node (ref "LCD") (pin "P$15") (pinfunction "XL_P$15") (pintype "bidirectional"))
    )
    (net (code "74") (name "unconnected-(LCD-XR-PadP$16)") (class "Default")
      (node (ref "LCD") (pin "P$16") (pinfunction "XR_P$16") (pintype "bidirectional"))
    )
    (net (code "75") (name "unconnected-(LCD-YD-PadP$17)") (class "Default")
      (node (ref "LCD") (pin "P$17") (pinfunction "YD_P$17") (pintype "bidirectional"))
    )
    (net (code "76") (name "unconnected-(LCD-YU-PadP$18)") (class "Default")
      (node (ref "LCD") (pin "P$18") (pinfunction "YU_P$18") (pintype "bidirectional"))
    )
    (net (code "77") (name "unconnected-(PWR-S-Pad3)") (class "Default")
      (node (ref "PWR") (pin "3") (pinfunction "S_3") (pintype "passive"))
    )
    (net (code "78") (name "unconnected-(SD_CARD-PadCD)") (class "Default")
      (node (ref "SD_CARD") (pin "CD") (pinfunction "CD_CD") (pintype "bidirectional"))
    )
    (net (code "79") (name "unconnected-(SD_CARD-PadDAT1)") (class "Default")
      (node (ref "SD_CARD") (pin "DAT1") (pinfunction "DAT1_DAT1") (pintype "bidirectional"))
    )
    (net (code "80") (name "unconnected-(SD_CARD-PadDAT2)") (class "Default")
      (node (ref "SD_CARD") (pin "DAT2") (pinfunction "DAT2_DAT2") (pintype "bidirectional"))
    )
    (net (code "81") (name "unconnected-(U$23-CTS-Pad9)") (class "Default")
      (node (ref "U$23") (pin "9") (pinfunction "CTS_9") (pintype "bidirectional"))
    )
    (net (code "82") (name "unconnected-(U$23-DCD-Pad12)") (class "Default")
      (node (ref "U$23") (pin "12") (pinfunction "DCD_12") (pintype "bidirectional"))
    )
    (net (code "83") (name "unconnected-(U$23-DSR-Pad10)") (class "Default")
      (node (ref "U$23") (pin "10") (pinfunction "DSR_10") (pintype "bidirectional"))
    )
    (net (code "84") (name "unconnected-(U$23-RI-Pad11)") (class "Default")
      (node (ref "U$23") (pin "11") (pinfunction "RI_11") (pintype "bidirectional"))
    )
    (net (code "85") (name "unconnected-(U$23-RS232-Pad15)") (class "Default")
      (node (ref "U$23") (pin "15") (pinfunction "RS232_15") (pintype "bidirectional"))
    )
  )
)
